# LVDS_IFC.net
KiCad netlist of a schematic drawn in Altium Designer
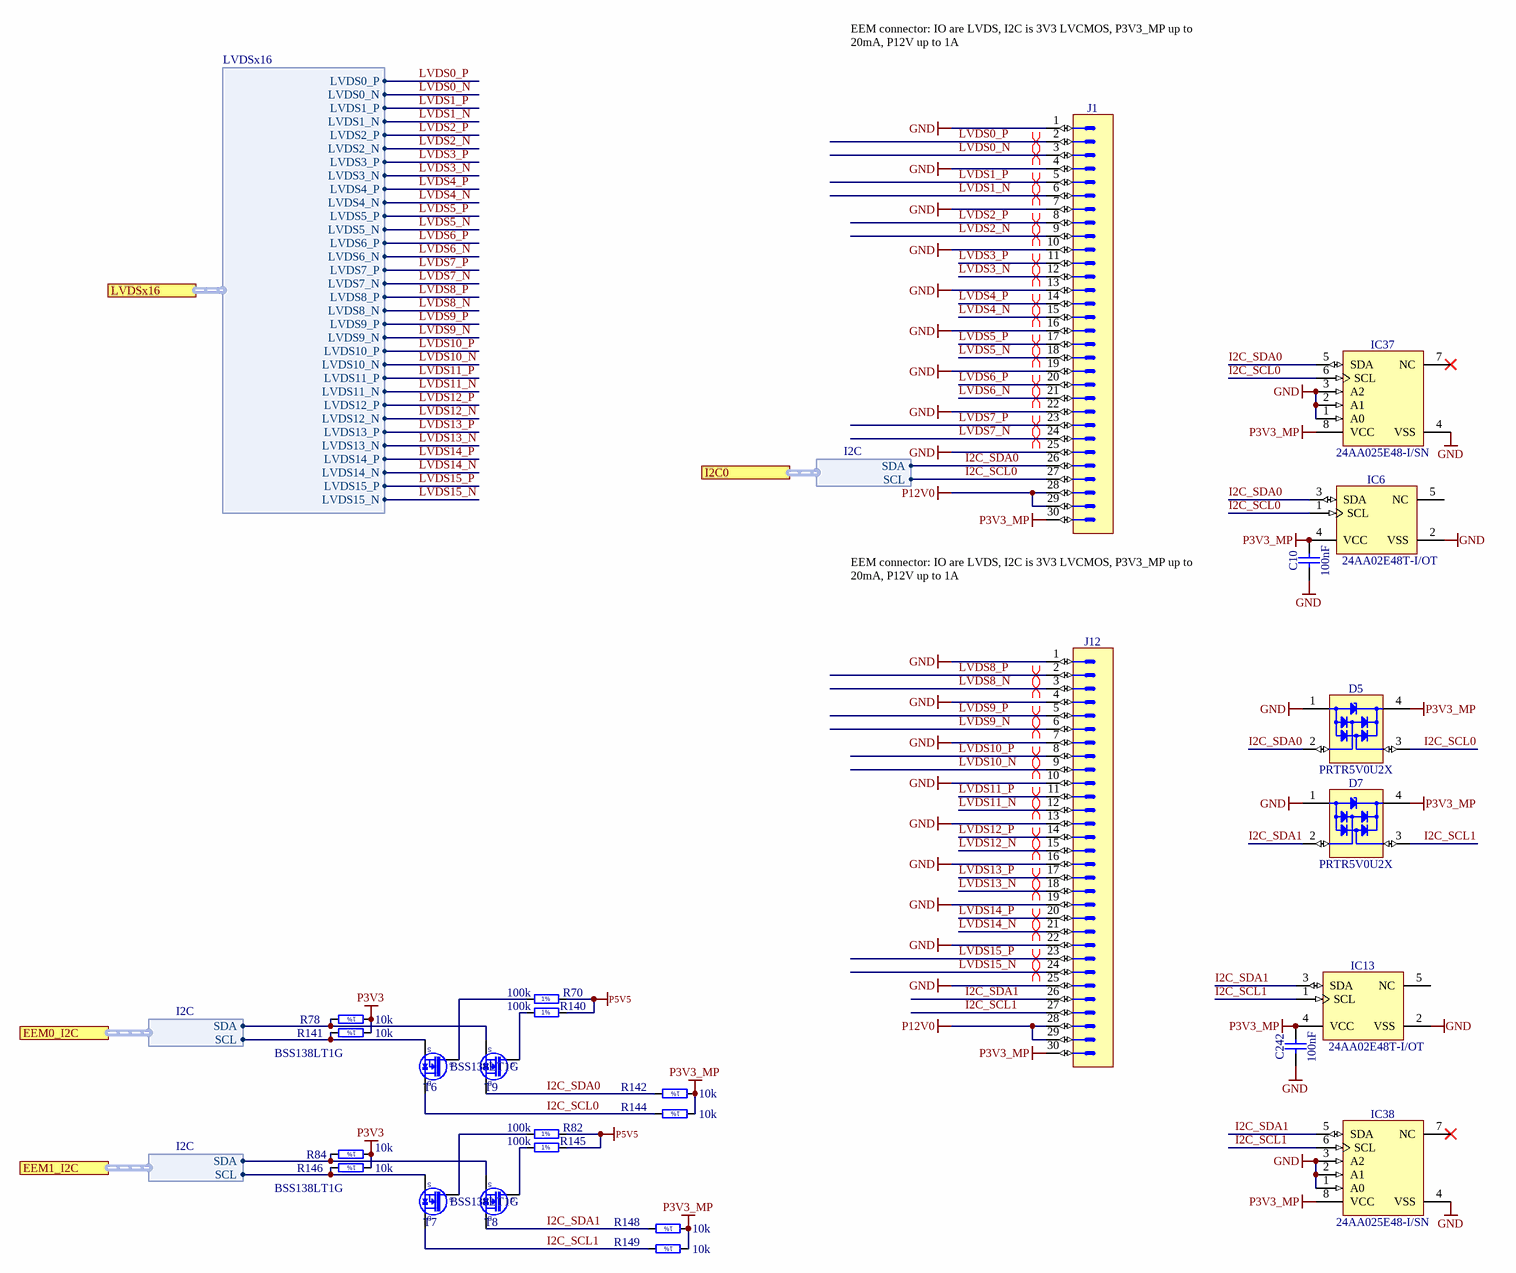
[diagram p0: LVDS_IFC.SchDoc]

(export (version "E")
  (design (tool "Eeschema 10.0.6"))
  (components
    (comp (ref "C10")
      (value "100nF")
      (footprint "CAPC1005X55N")
      (description "Non-polarised capacitor")
      (fields
        (field (name "PART NUMBER") "CC0402_100NF_16V_10%_X5R")
        (field (name "VOLTAGE") "16V")
        (field (name "AUTHOR") "CERN DEM JLC")
      )
      (libsource (lib "Capacitors") (part "Capacitor - non polarized"))
    )
    (comp (ref "C242")
      (value "100nF")
      (footprint "CAPC1005X55N")
      (description "Non-polarised capacitor")
      (fields
        (field (name "PART NUMBER") "CC0402_100NF_16V_10%_X5R")
        (field (name "VOLTAGE") "16V")
        (field (name "AUTHOR") "CERN DEM JLC")
      )
      (libsource (lib "Capacitors") (part "Capacitor - non polarized"))
    )
    (comp (ref "D5")
      (value "PRTR5V0U2X")
      (footprint "SOT190P230X110-4N")
      (description "Ultra Low Capacitance Double Rail-to-Rail ESD Protection Diode")
      (fields
        (field (name "VOLTAGE") "5.5V")
        (field (name "MANUFACTURER") "NXP SEMICONDUCTORS")
        (field (name "AUTHOR") "CERN DEM JLC")
      )
      (libsource (lib "ICs And Semiconductors") (part "PRTR5V0U2X"))
    )
    (comp (ref "D7")
      (value "PRTR5V0U2X")
      (footprint "SOT190P230X110-4N")
      (description "Ultra Low Capacitance Double Rail-to-Rail ESD Protection Diode")
      (fields
        (field (name "VOLTAGE") "5.5V")
        (field (name "MANUFACTURER") "NXP SEMICONDUCTORS")
        (field (name "AUTHOR") "CERN DEM JLC")
      )
      (libsource (lib "ICs And Semiconductors") (part "PRTR5V0U2X"))
    )
    (comp (ref "IC6")
      (value "24AA02E48T-I/OT")
      (footprint "SOT95P280X145-5N")
      (description "1.7V-5.5V, 2K I2C Serial EEPROM With EUI-48 Node Identity")
      (fields (field (name "MANUFACTURER") "MICROCHIP TECHNOLOGY") (field (name "AUTHOR") "CERN DEM MR"))
      (libsource (lib "ICs And Semiconductors") (part "24AA02E48T-I/OT"))
    )
    (comp (ref "IC13")
      (value "24AA02E48T-I/OT")
      (footprint "SOT95P280X145-5N")
      (description "1.7V-5.5V, 2K I2C Serial EEPROM With EUI-48 Node Identity")
      (fields (field (name "MANUFACTURER") "MICROCHIP TECHNOLOGY") (field (name "AUTHOR") "CERN DEM MR"))
      (libsource (lib "ICs And Semiconductors") (part "24AA02E48T-I/OT"))
    )
    (comp (ref "IC37")
      (value "24AA025E48-I/SN")
      (footprint "SOIC127P600X175-8N")
      (description "1.7V-5.5V, 2K I2C™ Serial EEPROMs with EUI-48™ Node Identity")
      (fields (field (name "MANUFACTURER") "MICROCHIP TECHNOLOGY") (field (name "AUTHOR") "CERN DEM MR"))
      (libsource (lib "ICs And Semiconductors") (part "24AA025E48-I/SN"))
    )
    (comp (ref "IC38")
      (value "24AA025E48-I/SN")
      (footprint "SOIC127P600X175-8N")
      (description "1.7V-5.5V, 2K I2C™ Serial EEPROMs with EUI-48™ Node Identity")
      (fields (field (name "MANUFACTURER") "MICROCHIP TECHNOLOGY") (field (name "AUTHOR") "CERN DEM MR"))
      (libsource (lib "ICs And Semiconductors") (part "24AA025E48-I/SN"))
    )
    (comp (ref "J1")
      (value "~")
      (footprint "3M_N2530-6002RB")
      (description "Connector 30 Male")
      (fields
        (field (name "PART NUMBER") "3M_N2530-6002RB")
        (field (name "MANUFACTURER") "3M")
        (field (name "AUTHOR") "CERN DEM JLC")
      )
      (libsource (lib "Connectors") (part "Connector 30 Male"))
    )
    (comp (ref "J12")
      (value "~")
      (footprint "3M_N2530-6002RB")
      (description "Connector 30 Male")
      (fields
        (field (name "PART NUMBER") "3M_N2530-6002RB")
        (field (name "MANUFACTURER") "3M")
        (field (name "AUTHOR") "CERN DEM JLC")
      )
      (libsource (lib "Connectors") (part "Connector 30 Male"))
    )
    (comp (ref "R70")
      (value "100k")
      (footprint "RESC1005X40N")
      (description "Resistor - 1%")
      (fields
        (field (name "PART NUMBER") "R0402_100K_1%_0.0625W_100PPM")
        (field (name "POWER") "0.0625W")
        (field (name "AUTHOR") "CERN DEM JLC")
      )
      (libsource (lib "Resistors") (part "Resistor - 1%"))
    )
    (comp (ref "R78")
      (value "10k")
      (footprint "RESC1005X40N")
      (description "Resistor - 1%")
      (fields
        (field (name "PART NUMBER") "R0402_10K_1%_0.0625W_100PPM")
        (field (name "POWER") "0.0625W")
        (field (name "AUTHOR") "CERN DEM JLC")
      )
      (libsource (lib "Resistors") (part "Resistor - 1%"))
    )
    (comp (ref "R82")
      (value "100k")
      (footprint "RESC1005X40N")
      (description "Resistor - 1%")
      (fields
        (field (name "PART NUMBER") "R0402_100K_1%_0.0625W_100PPM")
        (field (name "POWER") "0.0625W")
        (field (name "AUTHOR") "CERN DEM JLC")
      )
      (libsource (lib "Resistors") (part "Resistor - 1%"))
    )
    (comp (ref "R84")
      (value "10k")
      (footprint "RESC1005X40N")
      (description "Resistor - 1%")
      (fields
        (field (name "PART NUMBER") "R0402_10K_1%_0.0625W_100PPM")
        (field (name "POWER") "0.0625W")
        (field (name "AUTHOR") "CERN DEM JLC")
      )
      (libsource (lib "Resistors") (part "Resistor - 1%"))
    )
    (comp (ref "R140")
      (value "100k")
      (footprint "RESC1005X40N")
      (description "Resistor - 1%")
      (fields
        (field (name "PART NUMBER") "R0402_100K_1%_0.0625W_100PPM")
        (field (name "POWER") "0.0625W")
        (field (name "AUTHOR") "CERN DEM JLC")
      )
      (libsource (lib "Resistors") (part "Resistor - 1%"))
    )
    (comp (ref "R141")
      (value "10k")
      (footprint "RESC1005X40N")
      (description "Resistor - 1%")
      (fields
        (field (name "PART NUMBER") "R0402_10K_1%_0.0625W_100PPM")
        (field (name "POWER") "0.0625W")
        (field (name "AUTHOR") "CERN DEM JLC")
      )
      (libsource (lib "Resistors") (part "Resistor - 1%"))
    )
    (comp (ref "R142")
      (value "10k")
      (footprint "RESC1005X40N")
      (description "Resistor - 1%")
      (fields
        (field (name "PART NUMBER") "R0402_10K_1%_0.0625W_100PPM")
        (field (name "POWER") "0.0625W")
        (field (name "AUTHOR") "CERN DEM JLC")
      )
      (libsource (lib "Resistors") (part "Resistor - 1%"))
    )
    (comp (ref "R144")
      (value "10k")
      (footprint "RESC1005X40N")
      (description "Resistor - 1%")
      (fields
        (field (name "PART NUMBER") "R0402_10K_1%_0.0625W_100PPM")
        (field (name "POWER") "0.0625W")
        (field (name "AUTHOR") "CERN DEM JLC")
      )
      (libsource (lib "Resistors") (part "Resistor - 1%"))
    )
    (comp (ref "R145")
      (value "100k")
      (footprint "RESC1005X40N")
      (description "Resistor - 1%")
      (fields
        (field (name "PART NUMBER") "R0402_100K_1%_0.0625W_100PPM")
        (field (name "POWER") "0.0625W")
        (field (name "AUTHOR") "CERN DEM JLC")
      )
      (libsource (lib "Resistors") (part "Resistor - 1%"))
    )
    (comp (ref "R146")
      (value "10k")
      (footprint "RESC1005X40N")
      (description "Resistor - 1%")
      (fields
        (field (name "PART NUMBER") "R0402_10K_1%_0.0625W_100PPM")
        (field (name "POWER") "0.0625W")
        (field (name "AUTHOR") "CERN DEM JLC")
      )
      (libsource (lib "Resistors") (part "Resistor - 1%"))
    )
    (comp (ref "R148")
      (value "10k")
      (footprint "RESC1005X40N")
      (description "Resistor - 1%")
      (fields
        (field (name "PART NUMBER") "R0402_10K_1%_0.0625W_100PPM")
        (field (name "POWER") "0.0625W")
        (field (name "AUTHOR") "CERN DEM JLC")
      )
      (libsource (lib "Resistors") (part "Resistor - 1%"))
    )
    (comp (ref "R149")
      (value "10k")
      (footprint "RESC1005X40N")
      (description "Resistor - 1%")
      (fields
        (field (name "PART NUMBER") "R0402_10K_1%_0.0625W_100PPM")
        (field (name "POWER") "0.0625W")
        (field (name "AUTHOR") "CERN DEM JLC")
      )
      (libsource (lib "Resistors") (part "Resistor - 1%"))
    )
    (comp (ref "T6")
      (value "BSS138LT1G")
      (footprint "SOT95P240X110-3N")
      (description "N-CHANNEL MOSFET WITH DIODE")
      (fields (field (name "MANUFACTURER") "ON SEMICONDUCTOR") (field (name "AUTHOR") "CERN DEM JLC"))
      (libsource (lib "ICs And Semiconductors") (part "N-MOSFET-D 1G 2S 3D"))
    )
    (comp (ref "T7")
      (value "BSS138LT1G")
      (footprint "SOT95P240X110-3N")
      (description "N-CHANNEL MOSFET WITH DIODE")
      (fields (field (name "MANUFACTURER") "ON SEMICONDUCTOR") (field (name "AUTHOR") "CERN DEM JLC"))
      (libsource (lib "ICs And Semiconductors") (part "N-MOSFET-D 1G 2S 3D"))
    )
    (comp (ref "T8")
      (value "BSS138LT1G")
      (footprint "SOT95P240X110-3N")
      (description "N-CHANNEL MOSFET WITH DIODE")
      (fields (field (name "MANUFACTURER") "ON SEMICONDUCTOR") (field (name "AUTHOR") "CERN DEM JLC"))
      (libsource (lib "ICs And Semiconductors") (part "N-MOSFET-D 1G 2S 3D"))
    )
    (comp (ref "T9")
      (value "BSS138LT1G")
      (footprint "SOT95P240X110-3N")
      (description "N-CHANNEL MOSFET WITH DIODE")
      (fields (field (name "MANUFACTURER") "ON SEMICONDUCTOR") (field (name "AUTHOR") "CERN DEM JLC"))
      (libsource (lib "ICs And Semiconductors") (part "N-MOSFET-D 1G 2S 3D"))
    )
  )
  (nets
    (net (code "3") (name "/I2C_SCL0") (class "Default")
      (node (ref "D5") (pin "3") (pinfunction "I/O2_3") (pintype "bidirectional"))
      (node (ref "IC37") (pin "6") (pinfunction "SCL_6") (pintype "input"))
      (node (ref "IC6") (pin "1") (pinfunction "SCL_1") (pintype "input"))
      (node (ref "J1") (pin "27") (pinfunction "27_27") (pintype "bidirectional"))
      (node (ref "R144") (pin "2") (pinfunction "2_2") (pintype "passive"))
      (node (ref "T6") (pin "3") (pinfunction "D_3") (pintype "passive"))
    )
    (net (code "4") (name "/I2C_SCL1") (class "Default")
      (node (ref "D7") (pin "3") (pinfunction "I/O2_3") (pintype "bidirectional"))
      (node (ref "IC13") (pin "1") (pinfunction "SCL_1") (pintype "input"))
      (node (ref "IC38") (pin "6") (pinfunction "SCL_6") (pintype "input"))
      (node (ref "J12") (pin "27") (pinfunction "27_27") (pintype "bidirectional"))
      (node (ref "R149") (pin "2") (pinfunction "2_2") (pintype "passive"))
      (node (ref "T7") (pin "3") (pinfunction "D_3") (pintype "passive"))
    )
    (net (code "5") (name "/I2C_SDA0") (class "Default")
      (node (ref "D5") (pin "2") (pinfunction "I/O1_2") (pintype "bidirectional"))
      (node (ref "IC37") (pin "5") (pinfunction "SDA_5") (pintype "bidirectional"))
      (node (ref "IC6") (pin "3") (pinfunction "SDA_3") (pintype "bidirectional"))
      (node (ref "J1") (pin "26") (pinfunction "26_26") (pintype "bidirectional"))
      (node (ref "R142") (pin "2") (pinfunction "2_2") (pintype "passive"))
      (node (ref "T9") (pin "3") (pinfunction "D_3") (pintype "passive"))
    )
    (net (code "6") (name "/I2C_SDA1") (class "Default")
      (node (ref "D7") (pin "2") (pinfunction "I/O1_2") (pintype "bidirectional"))
      (node (ref "IC13") (pin "3") (pinfunction "SDA_3") (pintype "bidirectional"))
      (node (ref "IC38") (pin "5") (pinfunction "SDA_5") (pintype "bidirectional"))
      (node (ref "J12") (pin "26") (pinfunction "26_26") (pintype "bidirectional"))
      (node (ref "R148") (pin "2") (pinfunction "2_2") (pintype "passive"))
      (node (ref "T8") (pin "3") (pinfunction "D_3") (pintype "passive"))
    )
    (net (code "7") (name "/LVDS0_N") (class "Default")
      (node (ref "J1") (pin "3") (pinfunction "3_3") (pintype "bidirectional"))
    )
    (net (code "8") (name "/LVDS0_P") (class "Default")
      (node (ref "J1") (pin "2") (pinfunction "2_2") (pintype "bidirectional"))
    )
    (net (code "9") (name "/LVDS1_N") (class "Default")
      (node (ref "J1") (pin "6") (pinfunction "6_6") (pintype "bidirectional"))
    )
    (net (code "10") (name "/LVDS1_P") (class "Default")
      (node (ref "J1") (pin "5") (pinfunction "5_5") (pintype "bidirectional"))
    )
    (net (code "11") (name "/LVDS2_N") (class "Default")
      (node (ref "J1") (pin "9") (pinfunction "9_9") (pintype "bidirectional"))
    )
    (net (code "12") (name "/LVDS2_P") (class "Default")
      (node (ref "J1") (pin "8") (pinfunction "8_8") (pintype "bidirectional"))
    )
    (net (code "13") (name "/LVDS3_N") (class "Default")
      (node (ref "J1") (pin "12") (pinfunction "12_12") (pintype "bidirectional"))
    )
    (net (code "14") (name "/LVDS3_P") (class "Default")
      (node (ref "J1") (pin "11") (pinfunction "11_11") (pintype "bidirectional"))
    )
    (net (code "15") (name "/LVDS4_N") (class "Default")
      (node (ref "J1") (pin "15") (pinfunction "15_15") (pintype "bidirectional"))
    )
    (net (code "16") (name "/LVDS4_P") (class "Default")
      (node (ref "J1") (pin "14") (pinfunction "14_14") (pintype "bidirectional"))
    )
    (net (code "17") (name "/LVDS5_N") (class "Default")
      (node (ref "J1") (pin "18") (pinfunction "18_18") (pintype "bidirectional"))
    )
    (net (code "18") (name "/LVDS5_P") (class "Default")
      (node (ref "J1") (pin "17") (pinfunction "17_17") (pintype "bidirectional"))
    )
    (net (code "19") (name "/LVDS6_N") (class "Default")
      (node (ref "J1") (pin "21") (pinfunction "21_21") (pintype "bidirectional"))
    )
    (net (code "20") (name "/LVDS6_P") (class "Default")
      (node (ref "J1") (pin "20") (pinfunction "20_20") (pintype "bidirectional"))
    )
    (net (code "21") (name "/LVDS7_N") (class "Default")
      (node (ref "J1") (pin "24") (pinfunction "24_24") (pintype "bidirectional"))
    )
    (net (code "22") (name "/LVDS7_P") (class "Default")
      (node (ref "J1") (pin "23") (pinfunction "23_23") (pintype "bidirectional"))
    )
    (net (code "23") (name "/LVDS8_N") (class "Default")
      (node (ref "J12") (pin "3") (pinfunction "3_3") (pintype "bidirectional"))
    )
    (net (code "24") (name "/LVDS8_P") (class "Default")
      (node (ref "J12") (pin "2") (pinfunction "2_2") (pintype "bidirectional"))
    )
    (net (code "25") (name "/LVDS9_N") (class "Default")
      (node (ref "J12") (pin "6") (pinfunction "6_6") (pintype "bidirectional"))
    )
    (net (code "26") (name "/LVDS9_P") (class "Default")
      (node (ref "J12") (pin "5") (pinfunction "5_5") (pintype "bidirectional"))
    )
    (net (code "27") (name "/LVDS10_N") (class "Default")
      (node (ref "J12") (pin "9") (pinfunction "9_9") (pintype "bidirectional"))
    )
    (net (code "28") (name "/LVDS10_P") (class "Default")
      (node (ref "J12") (pin "8") (pinfunction "8_8") (pintype "bidirectional"))
    )
    (net (code "29") (name "/LVDS11_N") (class "Default")
      (node (ref "J12") (pin "12") (pinfunction "12_12") (pintype "bidirectional"))
    )
    (net (code "30") (name "/LVDS11_P") (class "Default")
      (node (ref "J12") (pin "11") (pinfunction "11_11") (pintype "bidirectional"))
    )
    (net (code "31") (name "/LVDS12_N") (class "Default")
      (node (ref "J12") (pin "15") (pinfunction "15_15") (pintype "bidirectional"))
    )
    (net (code "32") (name "/LVDS12_P") (class "Default")
      (node (ref "J12") (pin "14") (pinfunction "14_14") (pintype "bidirectional"))
    )
    (net (code "33") (name "/LVDS13_N") (class "Default")
      (node (ref "J12") (pin "18") (pinfunction "18_18") (pintype "bidirectional"))
    )
    (net (code "34") (name "/LVDS13_P") (class "Default")
      (node (ref "J12") (pin "17") (pinfunction "17_17") (pintype "bidirectional"))
    )
    (net (code "35") (name "/LVDS14_N") (class "Default")
      (node (ref "J12") (pin "21") (pinfunction "21_21") (pintype "bidirectional"))
    )
    (net (code "36") (name "/LVDS14_P") (class "Default")
      (node (ref "J12") (pin "20") (pinfunction "20_20") (pintype "bidirectional"))
    )
    (net (code "37") (name "/LVDS15_N") (class "Default")
      (node (ref "J12") (pin "24") (pinfunction "24_24") (pintype "bidirectional"))
    )
    (net (code "38") (name "/LVDS15_P") (class "Default")
      (node (ref "J12") (pin "23") (pinfunction "23_23") (pintype "bidirectional"))
    )
    (net (code "41") (name "GND") (class "Default")
      (node (ref "C10") (pin "1") (pinfunction "1_1") (pintype "passive"))
      (node (ref "C242") (pin "1") (pinfunction "1_1") (pintype "passive"))
      (node (ref "D5") (pin "1") (pinfunction "GND_1") (pintype "power_in"))
      (node (ref "D7") (pin "1") (pinfunction "GND_1") (pintype "power_in"))
      (node (ref "IC13") (pin "2") (pinfunction "VSS_2") (pintype "power_in"))
      (node (ref "IC37") (pin "1") (pinfunction "A0_1") (pintype "input"))
      (node (ref "IC37") (pin "2") (pinfunction "A1_2") (pintype "input"))
      (node (ref "IC37") (pin "3") (pinfunction "A2_3") (pintype "input"))
      (node (ref "IC37") (pin "4") (pinfunction "VSS_4") (pintype "power_in"))
      (node (ref "IC38") (pin "1") (pinfunction "A0_1") (pintype "input"))
      (node (ref "IC38") (pin "2") (pinfunction "A1_2") (pintype "input"))
      (node (ref "IC38") (pin "3") (pinfunction "A2_3") (pintype "input"))
      (node (ref "IC38") (pin "4") (pinfunction "VSS_4") (pintype "power_in"))
      (node (ref "IC6") (pin "2") (pinfunction "VSS_2") (pintype "power_in"))
      (node (ref "J1") (pin "1") (pinfunction "1_1") (pintype "bidirectional"))
      (node (ref "J1") (pin "10") (pinfunction "10_10") (pintype "bidirectional"))
      (node (ref "J1") (pin "13") (pinfunction "13_13") (pintype "bidirectional"))
      (node (ref "J1") (pin "16") (pinfunction "16_16") (pintype "bidirectional"))
      (node (ref "J1") (pin "19") (pinfunction "19_19") (pintype "bidirectional"))
      (node (ref "J1") (pin "22") (pinfunction "22_22") (pintype "bidirectional"))
      (node (ref "J1") (pin "25") (pinfunction "25_25") (pintype "bidirectional"))
      (node (ref "J1") (pin "4") (pinfunction "4_4") (pintype "bidirectional"))
      (node (ref "J1") (pin "7") (pinfunction "7_7") (pintype "bidirectional"))
      (node (ref "J12") (pin "1") (pinfunction "1_1") (pintype "bidirectional"))
      (node (ref "J12") (pin "10") (pinfunction "10_10") (pintype "bidirectional"))
      (node (ref "J12") (pin "13") (pinfunction "13_13") (pintype "bidirectional"))
      (node (ref "J12") (pin "16") (pinfunction "16_16") (pintype "bidirectional"))
      (node (ref "J12") (pin "19") (pinfunction "19_19") (pintype "bidirectional"))
      (node (ref "J12") (pin "22") (pinfunction "22_22") (pintype "bidirectional"))
      (node (ref "J12") (pin "25") (pinfunction "25_25") (pintype "bidirectional"))
      (node (ref "J12") (pin "4") (pinfunction "4_4") (pintype "bidirectional"))
      (node (ref "J12") (pin "7") (pinfunction "7_7") (pintype "bidirectional"))
    )
    (net (code "42") (name "Net-(T6-G)") (class "Default")
      (node (ref "R70") (pin "1") (pinfunction "1_1") (pintype "passive"))
      (node (ref "T6") (pin "1") (pinfunction "G_1") (pintype "passive"))
    )
    (net (code "43") (name "Net-(T6-S)") (class "Default")
      (node (ref "R141") (pin "2") (pinfunction "2_2") (pintype "passive"))
      (node (ref "T6") (pin "2") (pinfunction "S_2") (pintype "passive"))
    )
    (net (code "44") (name "Net-(T7-G)") (class "Default")
      (node (ref "R82") (pin "1") (pinfunction "1_1") (pintype "passive"))
      (node (ref "T7") (pin "1") (pinfunction "G_1") (pintype "passive"))
    )
    (net (code "45") (name "Net-(T7-S)") (class "Default")
      (node (ref "R146") (pin "2") (pinfunction "2_2") (pintype "passive"))
      (node (ref "T7") (pin "2") (pinfunction "S_2") (pintype "passive"))
    )
    (net (code "46") (name "Net-(T8-G)") (class "Default")
      (node (ref "R145") (pin "1") (pinfunction "1_1") (pintype "passive"))
      (node (ref "T8") (pin "1") (pinfunction "G_1") (pintype "passive"))
    )
    (net (code "47") (name "Net-(T8-S)") (class "Default")
      (node (ref "R84") (pin "2") (pinfunction "2_2") (pintype "passive"))
      (node (ref "T8") (pin "2") (pinfunction "S_2") (pintype "passive"))
    )
    (net (code "48") (name "Net-(T9-G)") (class "Default")
      (node (ref "R140") (pin "1") (pinfunction "1_1") (pintype "passive"))
      (node (ref "T9") (pin "1") (pinfunction "G_1") (pintype "passive"))
    )
    (net (code "49") (name "Net-(T9-S)") (class "Default")
      (node (ref "R78") (pin "2") (pinfunction "2_2") (pintype "passive"))
      (node (ref "T9") (pin "2") (pinfunction "S_2") (pintype "passive"))
    )
    (net (code "50") (name "P3V3") (class "Default")
      (node (ref "R141") (pin "1") (pinfunction "1_1") (pintype "passive"))
      (node (ref "R146") (pin "1") (pinfunction "1_1") (pintype "passive"))
      (node (ref "R78") (pin "1") (pinfunction "1_1") (pintype "passive"))
      (node (ref "R84") (pin "1") (pinfunction "1_1") (pintype "passive"))
    )
    (net (code "51") (name "P3V3_MP") (class "Default")
      (node (ref "C10") (pin "2") (pinfunction "2_2") (pintype "passive"))
      (node (ref "C242") (pin "2") (pinfunction "2_2") (pintype "passive"))
      (node (ref "D5") (pin "4") (pinfunction "VCC_4") (pintype "power_in"))
      (node (ref "D7") (pin "4") (pinfunction "VCC_4") (pintype "power_in"))
      (node (ref "IC13") (pin "4") (pinfunction "VCC_4") (pintype "power_in"))
      (node (ref "IC37") (pin "8") (pinfunction "VCC_8") (pintype "power_in"))
      (node (ref "IC38") (pin "8") (pinfunction "VCC_8") (pintype "power_in"))
      (node (ref "IC6") (pin "4") (pinfunction "VCC_4") (pintype "power_in"))
      (node (ref "J1") (pin "30") (pinfunction "30_30") (pintype "bidirectional"))
      (node (ref "J12") (pin "30") (pinfunction "30_30") (pintype "bidirectional"))
      (node (ref "R142") (pin "1") (pinfunction "1_1") (pintype "passive"))
      (node (ref "R144") (pin "1") (pinfunction "1_1") (pintype "passive"))
      (node (ref "R148") (pin "1") (pinfunction "1_1") (pintype "passive"))
      (node (ref "R149") (pin "1") (pinfunction "1_1") (pintype "passive"))
    )
    (net (code "52") (name "P5V5") (class "Default")
      (node (ref "R140") (pin "2") (pinfunction "2_2") (pintype "passive"))
      (node (ref "R145") (pin "2") (pinfunction "2_2") (pintype "passive"))
      (node (ref "R70") (pin "2") (pinfunction "2_2") (pintype "passive"))
      (node (ref "R82") (pin "2") (pinfunction "2_2") (pintype "passive"))
    )
    (net (code "53") (name "P12V0") (class "Default")
      (node (ref "J1") (pin "28") (pinfunction "28_28") (pintype "bidirectional"))
      (node (ref "J1") (pin "29") (pinfunction "29_29") (pintype "bidirectional"))
      (node (ref "J12") (pin "28") (pinfunction "28_28") (pintype "bidirectional"))
      (node (ref "J12") (pin "29") (pinfunction "29_29") (pintype "bidirectional"))
    )
    (net (code "54") (name "unconnected-(IC6-NC-Pad5)") (class "Default")
      (node (ref "IC6") (pin "5") (pinfunction "NC_5") (pintype "passive"))
    )
    (net (code "55") (name "unconnected-(IC13-NC-Pad5)") (class "Default")
      (node (ref "IC13") (pin "5") (pinfunction "NC_5") (pintype "passive"))
    )
    (net (code "56") (name "unconnected-(IC37-NC-Pad7)") (class "Default")
      (node (ref "IC37") (pin "7") (pinfunction "NC_7") (pintype "passive+no_connect"))
    )
    (net (code "57") (name "unconnected-(IC38-NC-Pad7)") (class "Default")
      (node (ref "IC38") (pin "7") (pinfunction "NC_7") (pintype "passive+no_connect"))
    )
  )
)
